# PhatNRF_MatrixKey.net
KiCad netlist of a schematic drawn in Altium Designer
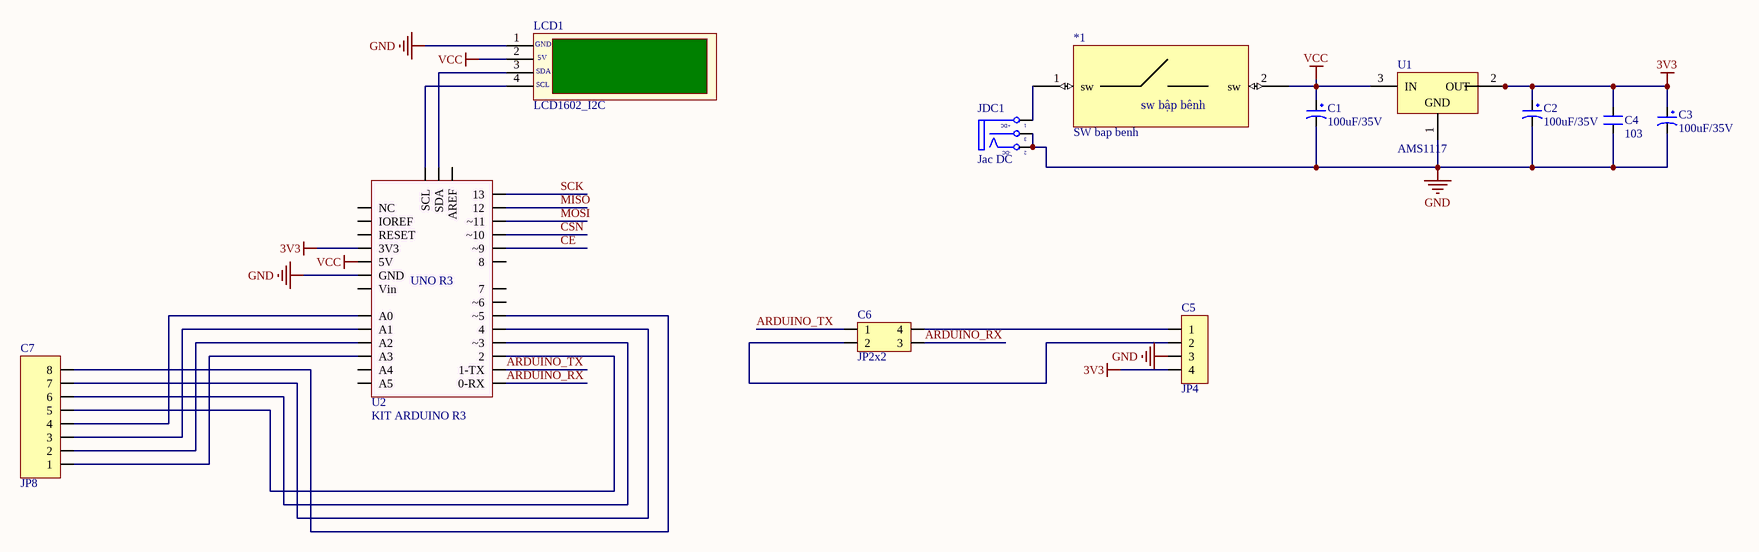
[diagram p0: PhatNRF_MatrixKey.SchDoc]

(export (version "E")
  (design (tool "Eeschema 10.0.6"))
  (components
    (comp (ref "*1")
      (value "SW bap benh")
      (footprint "SW bapbenh")
      (libsource (lib "Tesla_Thinh") (part "SW bap benh"))
    )
    (comp (ref "C1")
      (value "100uF/35V")
      (footprint "CP1.5/3.4")
      (description "Cap 100uF/35V - 470uF/16V")
      (libsource (lib "OBIT_TESLA") (part "CP3"))
    )
    (comp (ref "C2")
      (value "100uF/35V")
      (footprint "CP1.5/3.4")
      (description "Cap 100uF/35V - 470uF/16V")
      (libsource (lib "OBIT_TESLA") (part "CP3"))
    )
    (comp (ref "C3")
      (value "100uF/35V")
      (footprint "CP1.5/3.4")
      (description "Cap 100uF/35V - 470uF/16V")
      (libsource (lib "OBIT_TESLA") (part "CP3"))
    )
    (comp (ref "C4")
      (value "103")
      (footprint "SM-0805")
      (description "Cap SMD")
      (libsource (lib "OBIT_TESLA") (part "CM"))
    )
    (comp (ref "C5")
      (value "JP4")
      (footprint "JP4-C1T")
      (description "WR-PHD 2.54 mm Angled Socket Header")
      (fields
        (field (name "MANUFACTURER") "Würth Elektronik eiSos GmbH")
        (field (name "PARTNO") "613004143121")
        (field (name "CREATED BY") "Karrer Zheng")
      )
      (libsource (lib "OBIT_TESLA") (part "JP4"))
    )
    (comp (ref "C6")
      (value "JP2x2")
      (footprint "JP2-C2T")
      (description "WR-PHD 2.54 mm Dual Socket Header")
      (fields
        (field (name "MANUFACTURER") "Würth Elektronik eiSos GmbH")
        (field (name "PARTNO") "61300421821")
        (field (name "CREATED BY") "Karrer Zheng")
      )
      (libsource (lib "OBIT_TESLA") (part "JP2x2"))
    )
    (comp (ref "C7")
      (value "JP8")
      (footprint "JP8-C1C")
      (description "WR-PHD 2.54 mm Angled Socket Header")
      (fields
        (field (name "MANUFACTURER") "Würth Elektronik eiSos GmbH")
        (field (name "PARTNO") "613008143121")
        (field (name "CREATED BY") "Karrer Zheng")
      )
      (libsource (lib "OBIT_TESLA") (part "JP8"))
    )
    (comp (ref "JDC1")
      (value "Jac DC")
      (footprint "DC0")
      (description "Jac DC input")
      (libsource (lib "Tesla_Thinh") (part "DCIN"))
    )
    (comp (ref "LCD1")
      (value "LCD1602_I2C")
      (footprint "LCD1602_I2C")
      (libsource (lib "OBIT_TESLA") (part "LCD1602_I2C"))
    )
    (comp (ref "U1") (value "AMS1117") (footprint "SOT223") (libsource (lib "OBIT_TESLA") (part "AMS117")))
    (comp (ref "U2")
      (value "KIT ARDUINO R3")
      (footprint "Arduino UNO R3 - v1")
      (description "ARDUINO  R3 ATMEGA328, ARDUINO UNO, EVAL BOARD")
      (libsource (lib "MCU") (part "KIT ARDUINO R3"))
    )
  )
  (nets
    (net (code "1") (name "/ARDUINO_RX") (class "Default")
      (node (ref "C6") (pin "3") (pinfunction "3_3") (pintype "passive"))
      (node (ref "U2") (pin "0-RX") (pinfunction "0-RX_0-RX") (pintype "passive"))
    )
    (net (code "2") (name "/ARDUINO_TX") (class "Default")
      (node (ref "C6") (pin "1") (pinfunction "1_1") (pintype "passive"))
      (node (ref "U2") (pin "1-TX") (pinfunction "1-TX_1-TX") (pintype "passive"))
    )
    (net (code "3") (name "/CE") (class "Default")
      (node (ref "U2") (pin "~9") (pinfunction "~9_~9") (pintype "passive"))
    )
    (net (code "4") (name "/CSN") (class "Default")
      (node (ref "U2") (pin "~10") (pinfunction "~10_~10") (pintype "passive"))
    )
    (net (code "5") (name "/MISO") (class "Default")
      (node (ref "U2") (pin "12") (pinfunction "12_12") (pintype "passive"))
    )
    (net (code "6") (name "/MOSI") (class "Default")
      (node (ref "U2") (pin "~11") (pinfunction "~11_~11") (pintype "passive"))
    )
    (net (code "7") (name "/SCK") (class "Default")
      (node (ref "U2") (pin "13") (pinfunction "13_13") (pintype "passive"))
    )
    (net (code "8") (name "3V3") (class "Default")
      (node (ref "C2") (pin "1") (pinfunction "1_1") (pintype "passive"))
      (node (ref "C3") (pin "1") (pinfunction "1_1") (pintype "passive"))
      (node (ref "C4") (pin "2") (pinfunction "2_2") (pintype "passive"))
      (node (ref "C5") (pin "4") (pinfunction "4_4") (pintype "passive"))
      (node (ref "U1") (pin "2") (pinfunction "OUT_2") (pintype "power_in"))
      (node (ref "U1") (pin "4") (pinfunction "4_4") (pintype "passive"))
      (node (ref "U2") (pin "3V3") (pinfunction "3V3_3V3") (pintype "passive"))
    )
    (net (code "9") (name "GND") (class "Default")
      (node (ref "C1") (pin "2") (pinfunction "2_2") (pintype "passive"))
      (node (ref "C2") (pin "2") (pinfunction "2_2") (pintype "passive"))
      (node (ref "C3") (pin "2") (pinfunction "2_2") (pintype "passive"))
      (node (ref "C4") (pin "1") (pinfunction "1_1") (pintype "passive"))
      (node (ref "C5") (pin "3") (pinfunction "3_3") (pintype "passive"))
      (node (ref "JDC1") (pin "2") (pinfunction "TN_2") (pintype "passive"))
      (node (ref "JDC1") (pin "3") (pinfunction "S_3") (pintype "power_in"))
      (node (ref "LCD1") (pin "1") (pinfunction "GND_1") (pintype "passive"))
      (node (ref "U1") (pin "1") (pinfunction "GND_1") (pintype "power_in"))
      (node (ref "U2") (pin "GND") (pinfunction "GND_GND") (pintype "passive"))
    )
    (net (code "10") (name "Net-(C5-Pad1)") (class "Default")
      (node (ref "C5") (pin "1") (pinfunction "1_1") (pintype "passive"))
      (node (ref "C6") (pin "4") (pinfunction "4_4") (pintype "passive"))
    )
    (net (code "11") (name "Net-(C5-Pad2)") (class "Default")
      (node (ref "C5") (pin "2") (pinfunction "2_2") (pintype "passive"))
      (node (ref "C6") (pin "2") (pinfunction "2_2") (pintype "passive"))
    )
    (net (code "12") (name "Net-(C7-Pad1)") (class "Default")
      (node (ref "C7") (pin "1") (pinfunction "1_1") (pintype "passive"))
      (node (ref "U2") (pin "A3") (pinfunction "A3_A3") (pintype "passive"))
    )
    (net (code "13") (name "Net-(C7-Pad2)") (class "Default")
      (node (ref "C7") (pin "2") (pinfunction "2_2") (pintype "passive"))
      (node (ref "U2") (pin "A2") (pinfunction "A2_A2") (pintype "passive"))
    )
    (net (code "14") (name "Net-(C7-Pad3)") (class "Default")
      (node (ref "C7") (pin "3") (pinfunction "3_3") (pintype "passive"))
      (node (ref "U2") (pin "A1") (pinfunction "A1_A1") (pintype "passive"))
    )
    (net (code "15") (name "Net-(C7-Pad4)") (class "Default")
      (node (ref "C7") (pin "4") (pinfunction "4_4") (pintype "passive"))
      (node (ref "U2") (pin "A0") (pinfunction "A0_A0") (pintype "passive"))
    )
    (net (code "16") (name "Net-(C7-Pad5)") (class "Default")
      (node (ref "C7") (pin "5") (pinfunction "5_5") (pintype "passive"))
      (node (ref "U2") (pin "2") (pinfunction "2_2") (pintype "passive"))
    )
    (net (code "17") (name "Net-(C7-Pad6)") (class "Default")
      (node (ref "C7") (pin "6") (pinfunction "6_6") (pintype "passive"))
      (node (ref "U2") (pin "~3") (pinfunction "~3_~3") (pintype "passive"))
    )
    (net (code "18") (name "Net-(C7-Pad7)") (class "Default")
      (node (ref "C7") (pin "7") (pinfunction "7_7") (pintype "passive"))
      (node (ref "U2") (pin "4") (pinfunction "4_4") (pintype "passive"))
    )
    (net (code "19") (name "Net-(C7-Pad8)") (class "Default")
      (node (ref "C7") (pin "8") (pinfunction "8_8") (pintype "passive"))
      (node (ref "U2") (pin "~5") (pinfunction "~5_~5") (pintype "passive"))
    )
    (net (code "20") (name "Net-(JDC1-T)") (class "Default")
      (node (ref "*1") (pin "1") (pinfunction "sw_1") (pintype "bidirectional"))
      (node (ref "JDC1") (pin "1") (pinfunction "T_1") (pintype "passive"))
    )
    (net (code "21") (name "Net-(LCD1-SCL)") (class "Default")
      (node (ref "LCD1") (pin "4") (pinfunction "SCL_4") (pintype "passive"))
      (node (ref "U2") (pin "SCL") (pinfunction "SCL_SCL") (pintype "passive"))
    )
    (net (code "22") (name "Net-(LCD1-SDA)") (class "Default")
      (node (ref "LCD1") (pin "3") (pinfunction "SDA_3") (pintype "passive"))
      (node (ref "U2") (pin "SDA") (pinfunction "SDA_SDA") (pintype "passive"))
    )
    (net (code "23") (name "VCC") (class "Default")
      (node (ref "*1") (pin "2") (pinfunction "sw_2") (pintype "bidirectional"))
      (node (ref "C1") (pin "1") (pinfunction "1_1") (pintype "passive"))
      (node (ref "LCD1") (pin "2") (pinfunction "VCC_2") (pintype "passive"))
      (node (ref "U1") (pin "3") (pinfunction "IN_3") (pintype "power_in"))
      (node (ref "U2") (pin "5V") (pinfunction "5V_5V") (pintype "passive"))
    )
    (net (code "24") (name "unconnected-(U2-Pad7)") (class "Default")
      (node (ref "U2") (pin "7") (pinfunction "7_7") (pintype "passive"))
    )
    (net (code "25") (name "unconnected-(U2-Pad8)") (class "Default")
      (node (ref "U2") (pin "8") (pinfunction "8_8") (pintype "passive"))
    )
    (net (code "26") (name "unconnected-(U2-PadA4)") (class "Default")
      (node (ref "U2") (pin "A4") (pinfunction "A4_A4") (pintype "passive"))
    )
    (net (code "27") (name "unconnected-(U2-PadA5)") (class "Default")
      (node (ref "U2") (pin "A5") (pinfunction "A5_A5") (pintype "passive"))
    )
    (net (code "28") (name "unconnected-(U2-PadAREF)") (class "Default")
      (node (ref "U2") (pin "AREF") (pinfunction "AREF_AREF") (pintype "passive"))
    )
    (net (code "29") (name "unconnected-(U2-PadIOREF)") (class "Default")
      (node (ref "U2") (pin "IOREF") (pinfunction "IOREF_IOREF") (pintype "passive"))
    )
    (net (code "30") (name "unconnected-(U2-PadNC)") (class "Default")
      (node (ref "U2") (pin "NC") (pinfunction "NC_NC") (pintype "passive"))
    )
    (net (code "31") (name "unconnected-(U2-PadRESET)") (class "Default")
      (node (ref "U2") (pin "RESET") (pinfunction "RESET_RESET") (pintype "passive"))
    )
    (net (code "32") (name "unconnected-(U2-PadVin)") (class "Default")
      (node (ref "U2") (pin "Vin") (pinfunction "Vin_Vin") (pintype "passive"))
    )
    (net (code "33") (name "unconnected-(U2-Pad~6)") (class "Default")
      (node (ref "U2") (pin "~6") (pinfunction "~6_~6") (pintype "passive"))
    )
  )
)
